# Control_Board.net
KiCad netlist of a schematic drawn in EAGLE
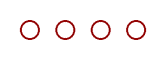
[diagram p0: schematic, sheet 1]
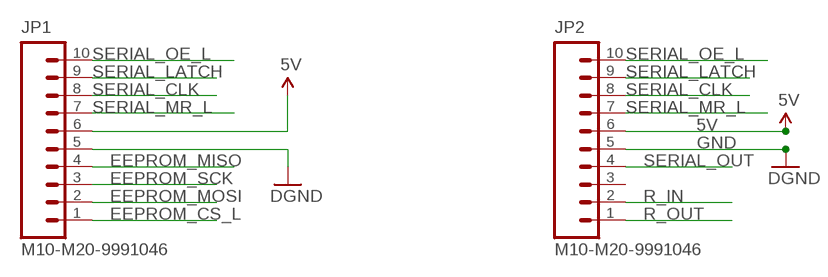
[diagram p1: schematic, sheet 2]
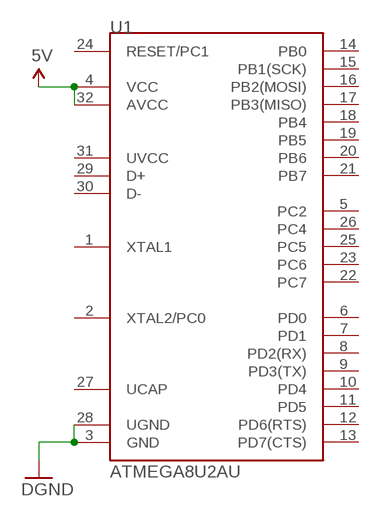
[diagram p2: schematic, sheet 3]

(export (version "E")
  (design (tool "Eeschema 10.0.6"))
  (components
    (comp (ref "JP1")
      (value "M10-M20-9991046")
      (footprint "eagle-import:M20-9991046")
      (libsource (lib "eagle-import") (part "M10-M20-9991046"))
    )
    (comp (ref "JP2")
      (value "M10-M20-9991046")
      (footprint "eagle-import:M20-9991046")
      (libsource (lib "eagle-import") (part "M10-M20-9991046"))
    )
    (comp (ref "STANDOFF1")
      (value "STAND-OFF")
      (footprint "eagle-import:STAND-OFF")
      (libsource (lib "eagle-import") (part "STAND-OFF"))
    )
    (comp (ref "STANDOFF2")
      (value "STAND-OFF")
      (footprint "eagle-import:STAND-OFF")
      (libsource (lib "eagle-import") (part "STAND-OFF"))
    )
    (comp (ref "STANDOFF3")
      (value "STAND-OFF")
      (footprint "eagle-import:STAND-OFF")
      (libsource (lib "eagle-import") (part "STAND-OFF"))
    )
    (comp (ref "STANDOFF4")
      (value "STAND-OFF")
      (footprint "eagle-import:STAND-OFF")
      (libsource (lib "eagle-import") (part "STAND-OFF"))
    )
    (comp (ref "U1")
      (value "ATMEGA8U2AU")
      (footprint "eagle-import:TQFP32-08")
      (libsource (lib "eagle-import") (part "ATMEGA8U2AU"))
    )
  )
  (nets
    (net (code "1") (name "5V") (class "Default")
      (node (ref "JP1") (pin "6") (pinfunction "6_6") (pintype "passive"))
      (node (ref "JP2") (pin "6") (pinfunction "6_6") (pintype "passive"))
      (node (ref "U1") (pin "32") (pinfunction "AVCC_32") (pintype "bidirectional"))
      (node (ref "U1") (pin "4") (pinfunction "VCC_4") (pintype "bidirectional"))
    )
    (net (code "2") (name "EEPROM_CS_L") (class "Default")
      (node (ref "JP1") (pin "1") (pinfunction "1_1") (pintype "passive"))
    )
    (net (code "3") (name "EEPROM_MISO") (class "Default")
      (node (ref "JP1") (pin "4") (pinfunction "4_4") (pintype "passive"))
    )
    (net (code "4") (name "EEPROM_MOSI") (class "Default")
      (node (ref "JP1") (pin "2") (pinfunction "2_2") (pintype "passive"))
    )
    (net (code "5") (name "EEPROM_SCK") (class "Default")
      (node (ref "JP1") (pin "3") (pinfunction "3_3") (pintype "passive"))
    )
    (net (code "6") (name "GND") (class "Default")
      (node (ref "JP1") (pin "5") (pinfunction "5_5") (pintype "passive"))
      (node (ref "JP2") (pin "5") (pinfunction "5_5") (pintype "passive"))
      (node (ref "U1") (pin "28") (pinfunction "UGND_28") (pintype "bidirectional"))
      (node (ref "U1") (pin "3") (pinfunction "GND_3") (pintype "bidirectional"))
    )
    (net (code "7") (name "R_IN") (class "Default")
      (node (ref "JP2") (pin "2") (pinfunction "2_2") (pintype "passive"))
    )
    (net (code "8") (name "R_OUT") (class "Default")
      (node (ref "JP2") (pin "1") (pinfunction "1_1") (pintype "passive"))
    )
    (net (code "9") (name "SERIAL_CLK") (class "Default")
      (node (ref "JP1") (pin "8") (pinfunction "8_8") (pintype "passive"))
      (node (ref "JP2") (pin "8") (pinfunction "8_8") (pintype "passive"))
    )
    (net (code "10") (name "SERIAL_LATCH") (class "Default")
      (node (ref "JP1") (pin "9") (pinfunction "9_9") (pintype "passive"))
      (node (ref "JP2") (pin "9") (pinfunction "9_9") (pintype "passive"))
    )
    (net (code "11") (name "SERIAL_MR_L") (class "Default")
      (node (ref "JP1") (pin "7") (pinfunction "7_7") (pintype "passive"))
      (node (ref "JP2") (pin "7") (pinfunction "7_7") (pintype "passive"))
    )
    (net (code "12") (name "SERIAL_OE_L") (class "Default")
      (node (ref "JP1") (pin "10") (pinfunction "10_10") (pintype "passive"))
      (node (ref "JP2") (pin "10") (pinfunction "10_10") (pintype "passive"))
    )
    (net (code "13") (name "SERIAL_OUT") (class "Default")
      (node (ref "JP2") (pin "4") (pinfunction "4_4") (pintype "passive"))
    )
    (net (code "14") (name "unconnected-(JP2-Pad3)") (class "Default")
      (node (ref "JP2") (pin "3") (pinfunction "3_3") (pintype "passive"))
    )
    (net (code "15") (name "unconnected-(U1-D+-Pad29)") (class "Default")
      (node (ref "U1") (pin "29") (pinfunction "D+_29") (pintype "bidirectional"))
    )
    (net (code "16") (name "unconnected-(U1-D--Pad30)") (class "Default")
      (node (ref "U1") (pin "30") (pinfunction "D-_30") (pintype "bidirectional"))
    )
    (net (code "17") (name "unconnected-(U1-PB0-Pad14)") (class "Default")
      (node (ref "U1") (pin "14") (pinfunction "PB0_14") (pintype "bidirectional"))
    )
    (net (code "18") (name "unconnected-(U1-PB1(SCK)-Pad15)") (class "Default")
      (node (ref "U1") (pin "15") (pinfunction "PB1(SCK)_15") (pintype "bidirectional"))
    )
    (net (code "19") (name "unconnected-(U1-PB2(MOSI)-Pad16)") (class "Default")
      (node (ref "U1") (pin "16") (pinfunction "PB2(MOSI)_16") (pintype "bidirectional"))
    )
    (net (code "20") (name "unconnected-(U1-PB3(MISO)-Pad17)") (class "Default")
      (node (ref "U1") (pin "17") (pinfunction "PB3(MISO)_17") (pintype "bidirectional"))
    )
    (net (code "21") (name "unconnected-(U1-PB4-Pad18)") (class "Default")
      (node (ref "U1") (pin "18") (pinfunction "PB4_18") (pintype "bidirectional"))
    )
    (net (code "22") (name "unconnected-(U1-PB5-Pad19)") (class "Default")
      (node (ref "U1") (pin "19") (pinfunction "PB5_19") (pintype "bidirectional"))
    )
    (net (code "23") (name "unconnected-(U1-PB6-Pad20)") (class "Default")
      (node (ref "U1") (pin "20") (pinfunction "PB6_20") (pintype "bidirectional"))
    )
    (net (code "24") (name "unconnected-(U1-PB7-Pad21)") (class "Default")
      (node (ref "U1") (pin "21") (pinfunction "PB7_21") (pintype "bidirectional"))
    )
    (net (code "25") (name "unconnected-(U1-PC2-Pad5)") (class "Default")
      (node (ref "U1") (pin "5") (pinfunction "PC2_5") (pintype "bidirectional"))
    )
    (net (code "26") (name "unconnected-(U1-PC4-Pad26)") (class "Default")
      (node (ref "U1") (pin "26") (pinfunction "PC4_26") (pintype "bidirectional"))
    )
    (net (code "27") (name "unconnected-(U1-PC5-Pad25)") (class "Default")
      (node (ref "U1") (pin "25") (pinfunction "PC5_25") (pintype "bidirectional"))
    )
    (net (code "28") (name "unconnected-(U1-PC6-Pad23)") (class "Default")
      (node (ref "U1") (pin "23") (pinfunction "PC6_23") (pintype "bidirectional"))
    )
    (net (code "29") (name "unconnected-(U1-PC7-Pad22)") (class "Default")
      (node (ref "U1") (pin "22") (pinfunction "PC7_22") (pintype "bidirectional"))
    )
    (net (code "30") (name "unconnected-(U1-PD0-Pad6)") (class "Default")
      (node (ref "U1") (pin "6") (pinfunction "PD0_6") (pintype "bidirectional"))
    )
    (net (code "31") (name "unconnected-(U1-PD1-Pad7)") (class "Default")
      (node (ref "U1") (pin "7") (pinfunction "PD1_7") (pintype "bidirectional"))
    )
    (net (code "32") (name "unconnected-(U1-PD2(RX)-Pad8)") (class "Default")
      (node (ref "U1") (pin "8") (pinfunction "PD2(RX)_8") (pintype "bidirectional"))
    )
    (net (code "33") (name "unconnected-(U1-PD3(TX)-Pad9)") (class "Default")
      (node (ref "U1") (pin "9") (pinfunction "PD3(TX)_9") (pintype "bidirectional"))
    )
    (net (code "34") (name "unconnected-(U1-PD4-Pad10)") (class "Default")
      (node (ref "U1") (pin "10") (pinfunction "PD4_10") (pintype "bidirectional"))
    )
    (net (code "35") (name "unconnected-(U1-PD5-Pad11)") (class "Default")
      (node (ref "U1") (pin "11") (pinfunction "PD5_11") (pintype "bidirectional"))
    )
    (net (code "36") (name "unconnected-(U1-PD6(RTS)-Pad12)") (class "Default")
      (node (ref "U1") (pin "12") (pinfunction "PD6(RTS)_12") (pintype "bidirectional"))
    )
    (net (code "37") (name "unconnected-(U1-PD7(CTS)-Pad13)") (class "Default")
      (node (ref "U1") (pin "13") (pinfunction "PD7(CTS)_13") (pintype "bidirectional"))
    )
    (net (code "38") (name "unconnected-(U1-RESET{slash}PC1-Pad24)") (class "Default")
      (node (ref "U1") (pin "24") (pinfunction "RESET/PC1_24") (pintype "bidirectional"))
    )
    (net (code "39") (name "unconnected-(U1-UCAP-Pad27)") (class "Default")
      (node (ref "U1") (pin "27") (pinfunction "UCAP_27") (pintype "bidirectional"))
    )
    (net (code "40") (name "unconnected-(U1-UVCC-Pad31)") (class "Default")
      (node (ref "U1") (pin "31") (pinfunction "UVCC_31") (pintype "bidirectional"))
    )
    (net (code "41") (name "unconnected-(U1-XTAL1-Pad1)") (class "Default")
      (node (ref "U1") (pin "1") (pinfunction "XTAL1_1") (pintype "bidirectional"))
    )
    (net (code "42") (name "unconnected-(U1-XTAL2{slash}PC0-Pad2)") (class "Default")
      (node (ref "U1") (pin "2") (pinfunction "XTAL2/PC0_2") (pintype "bidirectional"))
    )
  )
)
